# ADC.net
KiCad netlist of a schematic drawn in Altium Designer
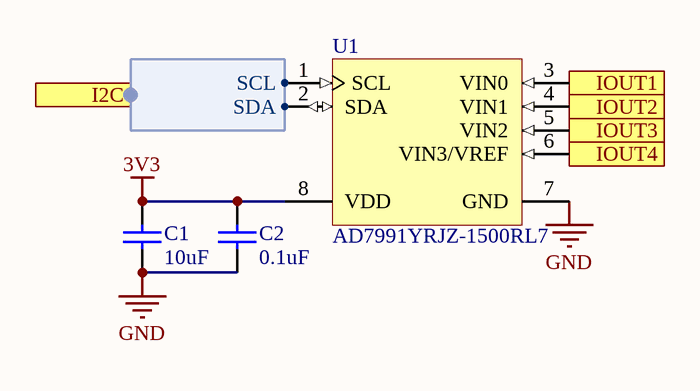
[diagram p0: ADC.SchDoc]

(export (version "E")
  (design (tool "Eeschema 10.0.6"))
  (components
    (comp (ref "C1")
      (value "10uF")
      (footprint "C0402[1005X55]")
      (description "10uF 6.3V 20% 0402 (1005 Metric)")
      (fields (field (name "PARTNUMBER") "GRM155R60J106ME44D") (field (name "MANUFACTURER") "Murata"))
      (libsource (lib "Capacitors") (part "CAP_10uF_6.3V_0402_20%"))
    )
    (comp (ref "C2")
      (value "0.1uF")
      (footprint "C0402[1005X55]")
      (description "0.1uF 6.3V 10% 0402 (1005 Metric)")
      (fields (field (name "PARTNUMBER") "GRM155R70J104KA01D") (field (name "MANUFACTURER") "Murata"))
      (libsource (lib "Capacitors") (part "CAP_0.1uF_6.3V_0402_10%"))
    )
    (comp (ref "U1")
      (value "AD7991YRJZ-1500RL7")
      (footprint "RJ-8_M")
      (fields (field (name "GENERIC PART NUMBER") "AD7991") (field (name "MANUFACTURER") "Analog Devices"))
      (libsource (lib "Altium Content Vault") (part "ADI-AD7991-RJ-8"))
    )
  )
  (nets
    (net (code "2") (name "/IOUT1") (class "Default")
      (node (ref "U1") (pin "3") (pinfunction "VIN0_3") (pintype "input"))
    )
    (net (code "3") (name "/IOUT2") (class "Default")
      (node (ref "U1") (pin "4") (pinfunction "VIN1_4") (pintype "input"))
    )
    (net (code "4") (name "/IOUT3") (class "Default")
      (node (ref "U1") (pin "5") (pinfunction "VIN2_5") (pintype "input"))
    )
    (net (code "5") (name "/IOUT4") (class "Default")
      (node (ref "U1") (pin "6") (pinfunction "VIN3/VREF_6") (pintype "input"))
    )
    (net (code "6") (name "/SCL") (class "Default")
      (node (ref "U1") (pin "1") (pinfunction "SCL_1") (pintype "input"))
    )
    (net (code "7") (name "/SDA") (class "Default")
      (node (ref "U1") (pin "2") (pinfunction "SDA_2") (pintype "bidirectional"))
    )
    (net (code "9") (name "3V3") (class "Default")
      (node (ref "C1") (pin "2") (pinfunction "2_2") (pintype "passive"))
      (node (ref "C2") (pin "2") (pinfunction "2_2") (pintype "passive"))
      (node (ref "U1") (pin "8") (pinfunction "VDD_8") (pintype "power_in"))
    )
    (net (code "10") (name "GND") (class "Default")
      (node (ref "C1") (pin "1") (pinfunction "1_1") (pintype "passive"))
      (node (ref "C2") (pin "1") (pinfunction "1_1") (pintype "passive"))
      (node (ref "U1") (pin "7") (pinfunction "GND_7") (pintype "power_in"))
    )
  )
)
